# cw312ttmp91fw_cardedge.net
KiCad netlist of a schematic drawn in Altium Designer
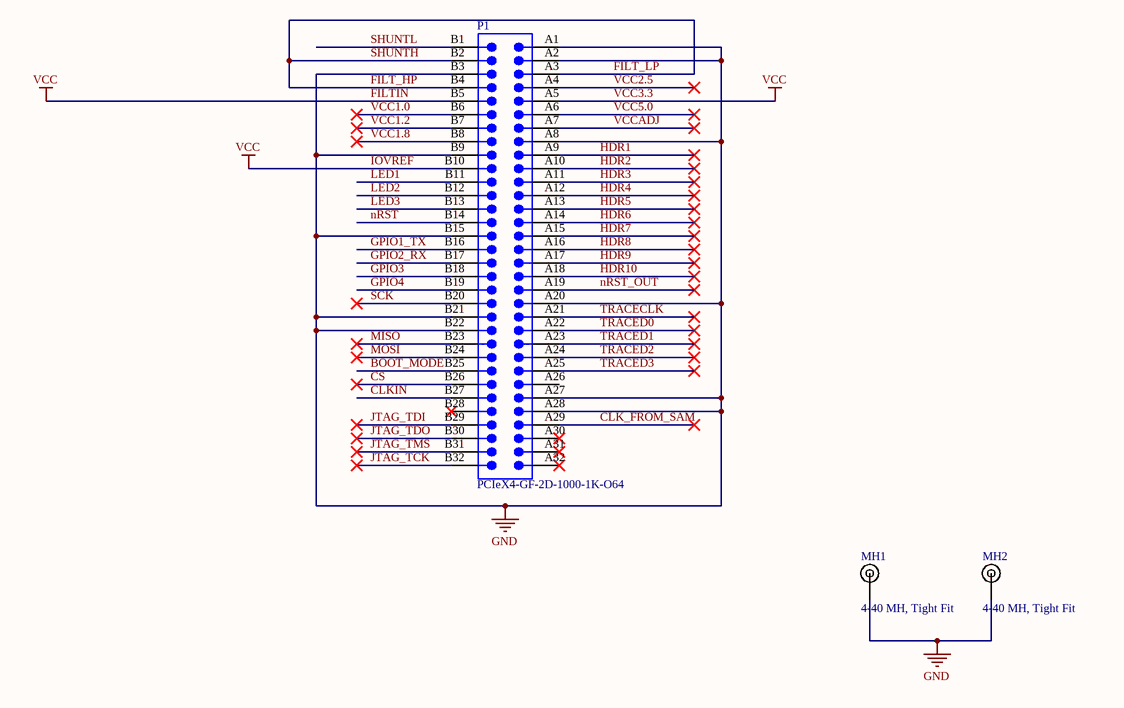
[diagram p0: cw312ttmp91fw_cardedge.SchDoc]

(export (version "E")
  (design (tool "Eeschema 10.0.6"))
  (components
    (comp (ref "MH1")
      (value "4-40 MH, Tight Fit")
      (footprint "MOUNT_#4_TIGHT")
      (description "Machine screw 4-40 Mounting Hole")
      (fields (field (name "PART NUMBER") "MOUNT_#4_TIGHT"))
      (libsource (lib "NewAE_AltiumLib") (part "Mounting_Hole"))
    )
    (comp (ref "MH2")
      (value "4-40 MH, Tight Fit")
      (footprint "MOUNT_#4_TIGHT")
      (description "Machine screw 4-40 Mounting Hole")
      (fields (field (name "PART NUMBER") "MOUNT_#4_TIGHT"))
      (libsource (lib "NewAE_AltiumLib") (part "Mounting_Hole"))
    )
    (comp (ref "P1")
      (value "PCIeX4-GF-2D-1000-1K-O64")
      (footprint "PCIeX4-GF-2D-1000-1K-O64")
      (description "Golden finger, PCIeX4, Dual, Opposite, Pitch 1mm, 64-Position")
      (fields (field (name "PUBLISHER") "Altium"))
      (libsource (lib "Altium Content Vault") (part "PCIeX4-GF-2D-1000-1K-O64"))
    )
  )
  (nets
    (net (code "1") (name "/BOOT_MODE") (class "Default")
      (node (ref "P1") (pin "B25") (pinfunction "B25_B25") (pintype "passive"))
    )
    (net (code "2") (name "/CLKIN") (class "Default")
      (node (ref "P1") (pin "B27") (pinfunction "B27_B27") (pintype "passive"))
    )
    (net (code "3") (name "/CLK_FROM_SAM") (class "Default")
      (node (ref "P1") (pin "A29") (pinfunction "A29_A29") (pintype "passive+no_connect"))
    )
    (net (code "4") (name "/CS") (class "Default")
      (node (ref "P1") (pin "B26") (pinfunction "B26_B26") (pintype "passive+no_connect"))
    )
    (net (code "5") (name "/FILT_HP") (class "Default")
      (node (ref "P1") (pin "A3") (pinfunction "A3_A3") (pintype "passive"))
      (node (ref "P1") (pin "B2") (pinfunction "B2_B2") (pintype "passive"))
      (node (ref "P1") (pin "B4") (pinfunction "B4_B4") (pintype "passive"))
    )
    (net (code "6") (name "/GPIO1_TX") (class "Default")
      (node (ref "P1") (pin "B16") (pinfunction "B16_B16") (pintype "passive"))
    )
    (net (code "7") (name "/GPIO2_RX") (class "Default")
      (node (ref "P1") (pin "B17") (pinfunction "B17_B17") (pintype "passive"))
    )
    (net (code "8") (name "/GPIO3") (class "Default")
      (node (ref "P1") (pin "B18") (pinfunction "B18_B18") (pintype "passive"))
    )
    (net (code "9") (name "/GPIO4") (class "Default")
      (node (ref "P1") (pin "B19") (pinfunction "B19_B19") (pintype "passive"))
    )
    (net (code "10") (name "/HDR1") (class "Default")
      (node (ref "P1") (pin "A9") (pinfunction "A9_A9") (pintype "passive+no_connect"))
    )
    (net (code "11") (name "/HDR2") (class "Default")
      (node (ref "P1") (pin "A10") (pinfunction "A10_A10") (pintype "passive+no_connect"))
    )
    (net (code "12") (name "/HDR3") (class "Default")
      (node (ref "P1") (pin "A11") (pinfunction "A11_A11") (pintype "passive+no_connect"))
    )
    (net (code "13") (name "/HDR4") (class "Default")
      (node (ref "P1") (pin "A12") (pinfunction "A12_A12") (pintype "passive+no_connect"))
    )
    (net (code "14") (name "/HDR5") (class "Default")
      (node (ref "P1") (pin "A13") (pinfunction "A13_A13") (pintype "passive+no_connect"))
    )
    (net (code "15") (name "/HDR6") (class "Default")
      (node (ref "P1") (pin "A14") (pinfunction "A14_A14") (pintype "passive+no_connect"))
    )
    (net (code "16") (name "/HDR7") (class "Default")
      (node (ref "P1") (pin "A15") (pinfunction "A15_A15") (pintype "passive+no_connect"))
    )
    (net (code "17") (name "/HDR8") (class "Default")
      (node (ref "P1") (pin "A16") (pinfunction "A16_A16") (pintype "passive+no_connect"))
    )
    (net (code "18") (name "/HDR9") (class "Default")
      (node (ref "P1") (pin "A17") (pinfunction "A17_A17") (pintype "passive+no_connect"))
    )
    (net (code "19") (name "/HDR10") (class "Default")
      (node (ref "P1") (pin "A18") (pinfunction "A18_A18") (pintype "passive+no_connect"))
    )
    (net (code "20") (name "/JTAG_TCK") (class "Default")
      (node (ref "P1") (pin "B32") (pinfunction "B32_B32") (pintype "passive+no_connect"))
    )
    (net (code "21") (name "/JTAG_TDI") (class "Default")
      (node (ref "P1") (pin "B29") (pinfunction "B29_B29") (pintype "passive+no_connect"))
    )
    (net (code "22") (name "/JTAG_TDO") (class "Default")
      (node (ref "P1") (pin "B30") (pinfunction "B30_B30") (pintype "passive+no_connect"))
    )
    (net (code "23") (name "/JTAG_TMS") (class "Default")
      (node (ref "P1") (pin "B31") (pinfunction "B31_B31") (pintype "passive+no_connect"))
    )
    (net (code "24") (name "/LED1") (class "Default")
      (node (ref "P1") (pin "B11") (pinfunction "B11_B11") (pintype "passive"))
    )
    (net (code "25") (name "/LED2") (class "Default")
      (node (ref "P1") (pin "B12") (pinfunction "B12_B12") (pintype "passive"))
    )
    (net (code "26") (name "/LED3") (class "Default")
      (node (ref "P1") (pin "B13") (pinfunction "B13_B13") (pintype "passive"))
    )
    (net (code "27") (name "/MISO") (class "Default")
      (node (ref "P1") (pin "B23") (pinfunction "B23_B23") (pintype "passive+no_connect"))
    )
    (net (code "28") (name "/MOSI") (class "Default")
      (node (ref "P1") (pin "B24") (pinfunction "B24_B24") (pintype "passive+no_connect"))
    )
    (net (code "29") (name "/SCK") (class "Default")
      (node (ref "P1") (pin "B20") (pinfunction "B20_B20") (pintype "passive+no_connect"))
    )
    (net (code "30") (name "/SHUNTL") (class "Default")
      (node (ref "P1") (pin "B1") (pinfunction "B1_B1") (pintype "passive"))
    )
    (net (code "31") (name "/TRACECLK") (class "Default")
      (node (ref "P1") (pin "A21") (pinfunction "A21_A21") (pintype "passive+no_connect"))
    )
    (net (code "32") (name "/TRACED0") (class "Default")
      (node (ref "P1") (pin "A22") (pinfunction "A22_A22") (pintype "passive+no_connect"))
    )
    (net (code "33") (name "/TRACED1") (class "Default")
      (node (ref "P1") (pin "A23") (pinfunction "A23_A23") (pintype "passive+no_connect"))
    )
    (net (code "34") (name "/TRACED2") (class "Default")
      (node (ref "P1") (pin "A24") (pinfunction "A24_A24") (pintype "passive+no_connect"))
    )
    (net (code "35") (name "/TRACED3") (class "Default")
      (node (ref "P1") (pin "A25") (pinfunction "A25_A25") (pintype "passive+no_connect"))
    )
    (net (code "36") (name "/VCC1.0") (class "Default")
      (node (ref "P1") (pin "B6") (pinfunction "B6_B6") (pintype "passive+no_connect"))
    )
    (net (code "37") (name "/VCC1.2") (class "Default")
      (node (ref "P1") (pin "B7") (pinfunction "B7_B7") (pintype "passive+no_connect"))
    )
    (net (code "38") (name "/VCC1.8") (class "Default")
      (node (ref "P1") (pin "B8") (pinfunction "B8_B8") (pintype "passive+no_connect"))
    )
    (net (code "39") (name "/VCC2.5") (class "Default")
      (node (ref "P1") (pin "A4") (pinfunction "A4_A4") (pintype "passive+no_connect"))
    )
    (net (code "40") (name "/VCC5.0") (class "Default")
      (node (ref "P1") (pin "A6") (pinfunction "A6_A6") (pintype "passive+no_connect"))
    )
    (net (code "41") (name "/VCCADJ") (class "Default")
      (node (ref "P1") (pin "A7") (pinfunction "A7_A7") (pintype "passive+no_connect"))
    )
    (net (code "42") (name "/nRST") (class "Default")
      (node (ref "P1") (pin "B14") (pinfunction "B14_B14") (pintype "passive"))
    )
    (net (code "43") (name "/nRST_OUT") (class "Default")
      (node (ref "P1") (pin "A19") (pinfunction "A19_A19") (pintype "passive+no_connect"))
    )
    (net (code "44") (name "GND") (class "Default")
      (node (ref "MH1") (pin "1") (pinfunction "1_1") (pintype "passive"))
      (node (ref "MH2") (pin "1") (pinfunction "1_1") (pintype "passive"))
      (node (ref "P1") (pin "A1") (pinfunction "A1_A1") (pintype "passive"))
      (node (ref "P1") (pin "A2") (pinfunction "A2_A2") (pintype "passive"))
      (node (ref "P1") (pin "A20") (pinfunction "A20_A20") (pintype "passive"))
      (node (ref "P1") (pin "A27") (pinfunction "A27_A27") (pintype "passive"))
      (node (ref "P1") (pin "A28") (pinfunction "A28_A28") (pintype "passive"))
      (node (ref "P1") (pin "A8") (pinfunction "A8_A8") (pintype "passive"))
      (node (ref "P1") (pin "B15") (pinfunction "B15_B15") (pintype "passive"))
      (node (ref "P1") (pin "B21") (pinfunction "B21_B21") (pintype "passive"))
      (node (ref "P1") (pin "B22") (pinfunction "B22_B22") (pintype "passive"))
      (node (ref "P1") (pin "B3") (pinfunction "B3_B3") (pintype "passive"))
      (node (ref "P1") (pin "B9") (pinfunction "B9_B9") (pintype "passive"))
    )
    (net (code "45") (name "VCC") (class "Default")
      (node (ref "P1") (pin "A5") (pinfunction "A5_A5") (pintype "passive"))
      (node (ref "P1") (pin "B10") (pinfunction "B10_B10") (pintype "passive"))
      (node (ref "P1") (pin "B5") (pinfunction "B5_B5") (pintype "passive"))
    )
    (net (code "46") (name "unconnected-(P1-PadA26)") (class "Default")
      (node (ref "P1") (pin "A26") (pinfunction "A26_A26") (pintype "passive"))
    )
    (net (code "47") (name "unconnected-(P1-PadA30)") (class "Default")
      (node (ref "P1") (pin "A30") (pinfunction "A30_A30") (pintype "passive+no_connect"))
    )
    (net (code "48") (name "unconnected-(P1-PadA31)") (class "Default")
      (node (ref "P1") (pin "A31") (pinfunction "A31_A31") (pintype "passive+no_connect"))
    )
    (net (code "49") (name "unconnected-(P1-PadA32)") (class "Default")
      (node (ref "P1") (pin "A32") (pinfunction "A32_A32") (pintype "passive+no_connect"))
    )
    (net (code "50") (name "unconnected-(P1-PadB28)") (class "Default")
      (node (ref "P1") (pin "B28") (pinfunction "B28_B28") (pintype "passive+no_connect"))
    )
  )
)
